# Sensors.net
KiCad netlist of a schematic drawn in Altium Designer
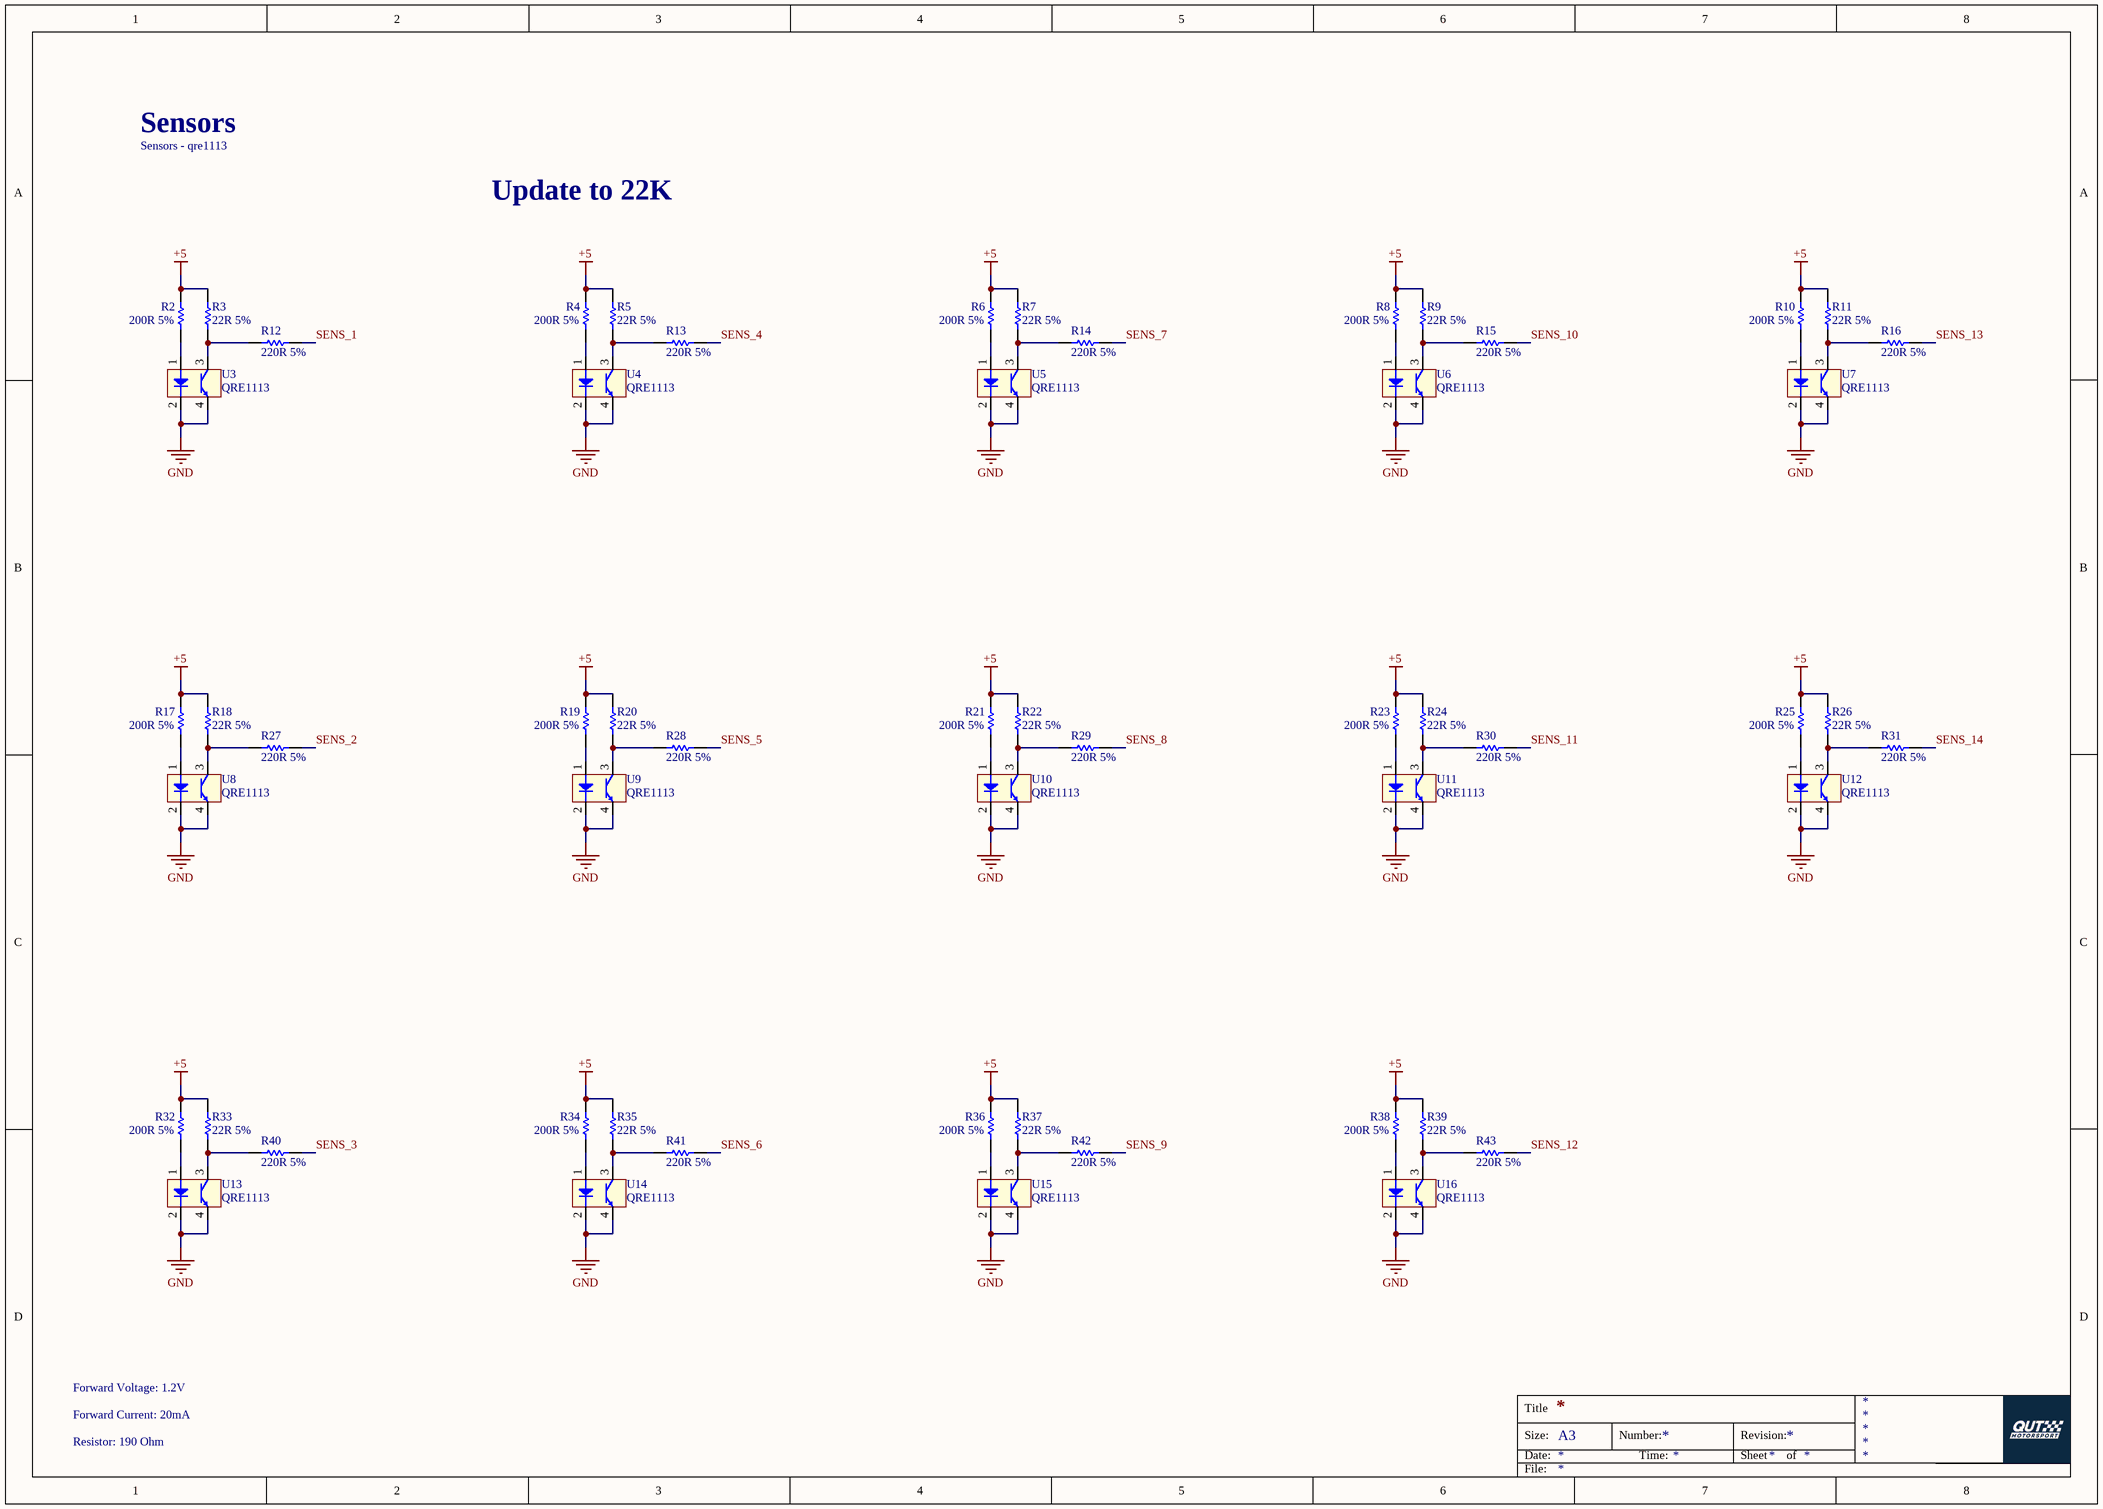
[diagram p0: Sensors.SchDoc]

(export (version "E")
  (design (tool "Eeschema 10.0.6"))
  (components
    (comp (ref "R2")
      (value "200R 5%")
      (footprint "RESC0603(1608)_L")
      (description "200R 0.1W 5% 0603 (1608 Metric)  SMD")
      (fields (field (name "TOLERANCE") "5 %") (field (name "POWER") "0.1 W"))
      (libsource (lib "Altium Content Vault") (part "RES"))
    )
    (comp (ref "R3")
      (value "22R 5%")
      (footprint "RESC0603(1608)_N")
      (description "22R 0.1W 5% 0603 (1608 Metric)  SMD")
      (fields (field (name "POWER") "0.1 W") (field (name "TOLERANCE") "5 %"))
      (libsource (lib "Altium Content Vault") (part "RES"))
    )
    (comp (ref "R4")
      (value "200R 5%")
      (footprint "RESC0603(1608)_L")
      (description "200R 0.1W 5% 0603 (1608 Metric)  SMD")
      (fields (field (name "TOLERANCE") "5 %") (field (name "POWER") "0.1 W"))
      (libsource (lib "Altium Content Vault") (part "RES"))
    )
    (comp (ref "R5")
      (value "22R 5%")
      (footprint "RESC0603(1608)_N")
      (description "22R 0.1W 5% 0603 (1608 Metric)  SMD")
      (fields (field (name "POWER") "0.1 W") (field (name "TOLERANCE") "5 %"))
      (libsource (lib "Altium Content Vault") (part "RES"))
    )
    (comp (ref "R6")
      (value "200R 5%")
      (footprint "RESC0603(1608)_L")
      (description "200R 0.1W 5% 0603 (1608 Metric)  SMD")
      (fields (field (name "TOLERANCE") "5 %") (field (name "POWER") "0.1 W"))
      (libsource (lib "Altium Content Vault") (part "RES"))
    )
    (comp (ref "R7")
      (value "22R 5%")
      (footprint "RESC0603(1608)_N")
      (description "22R 0.1W 5% 0603 (1608 Metric)  SMD")
      (fields (field (name "POWER") "0.1 W") (field (name "TOLERANCE") "5 %"))
      (libsource (lib "Altium Content Vault") (part "RES"))
    )
    (comp (ref "R8")
      (value "200R 5%")
      (footprint "RESC0603(1608)_L")
      (description "200R 0.1W 5% 0603 (1608 Metric)  SMD")
      (fields (field (name "TOLERANCE") "5 %") (field (name "POWER") "0.1 W"))
      (libsource (lib "Altium Content Vault") (part "RES"))
    )
    (comp (ref "R9")
      (value "22R 5%")
      (footprint "RESC0603(1608)_N")
      (description "22R 0.1W 5% 0603 (1608 Metric)  SMD")
      (fields (field (name "POWER") "0.1 W") (field (name "TOLERANCE") "5 %"))
      (libsource (lib "Altium Content Vault") (part "RES"))
    )
    (comp (ref "R10")
      (value "200R 5%")
      (footprint "RESC0603(1608)_L")
      (description "200R 0.1W 5% 0603 (1608 Metric)  SMD")
      (fields (field (name "TOLERANCE") "5 %") (field (name "POWER") "0.1 W"))
      (libsource (lib "Altium Content Vault") (part "RES"))
    )
    (comp (ref "R11")
      (value "22R 5%")
      (footprint "RESC0603(1608)_N")
      (description "22R 0.1W 5% 0603 (1608 Metric)  SMD")
      (fields (field (name "POWER") "0.1 W") (field (name "TOLERANCE") "5 %"))
      (libsource (lib "Altium Content Vault") (part "RES"))
    )
    (comp (ref "R12")
      (value "220R 5%")
      (footprint "RESC0603(1608)_M")
      (description "220R 0.1W 5% 0603 (1608 Metric)  SMD")
      (fields (field (name "POWER") "0.1 W") (field (name "TOLERANCE") "5 %"))
      (libsource (lib "Altium Content Vault") (part "RES"))
    )
    (comp (ref "R13")
      (value "220R 5%")
      (footprint "RESC0603(1608)_M")
      (description "220R 0.1W 5% 0603 (1608 Metric)  SMD")
      (fields (field (name "POWER") "0.1 W") (field (name "TOLERANCE") "5 %"))
      (libsource (lib "Altium Content Vault") (part "RES"))
    )
    (comp (ref "R14")
      (value "220R 5%")
      (footprint "RESC0603(1608)_M")
      (description "220R 0.1W 5% 0603 (1608 Metric)  SMD")
      (fields (field (name "POWER") "0.1 W") (field (name "TOLERANCE") "5 %"))
      (libsource (lib "Altium Content Vault") (part "RES"))
    )
    (comp (ref "R15")
      (value "220R 5%")
      (footprint "RESC0603(1608)_M")
      (description "220R 0.1W 5% 0603 (1608 Metric)  SMD")
      (fields (field (name "POWER") "0.1 W") (field (name "TOLERANCE") "5 %"))
      (libsource (lib "Altium Content Vault") (part "RES"))
    )
    (comp (ref "R16")
      (value "220R 5%")
      (footprint "RESC0603(1608)_M")
      (description "220R 0.1W 5% 0603 (1608 Metric)  SMD")
      (fields (field (name "POWER") "0.1 W") (field (name "TOLERANCE") "5 %"))
      (libsource (lib "Altium Content Vault") (part "RES"))
    )
    (comp (ref "R17")
      (value "200R 5%")
      (footprint "RESC0603(1608)_L")
      (description "200R 0.1W 5% 0603 (1608 Metric)  SMD")
      (fields (field (name "TOLERANCE") "5 %") (field (name "POWER") "0.1 W"))
      (libsource (lib "Altium Content Vault") (part "RES"))
    )
    (comp (ref "R18")
      (value "22R 5%")
      (footprint "RESC0603(1608)_N")
      (description "22R 0.1W 5% 0603 (1608 Metric)  SMD")
      (fields (field (name "POWER") "0.1 W") (field (name "TOLERANCE") "5 %"))
      (libsource (lib "Altium Content Vault") (part "RES"))
    )
    (comp (ref "R19")
      (value "200R 5%")
      (footprint "RESC0603(1608)_L")
      (description "200R 0.1W 5% 0603 (1608 Metric)  SMD")
      (fields (field (name "TOLERANCE") "5 %") (field (name "POWER") "0.1 W"))
      (libsource (lib "Altium Content Vault") (part "RES"))
    )
    (comp (ref "R20")
      (value "22R 5%")
      (footprint "RESC0603(1608)_N")
      (description "22R 0.1W 5% 0603 (1608 Metric)  SMD")
      (fields (field (name "POWER") "0.1 W") (field (name "TOLERANCE") "5 %"))
      (libsource (lib "Altium Content Vault") (part "RES"))
    )
    (comp (ref "R21")
      (value "200R 5%")
      (footprint "RESC0603(1608)_L")
      (description "200R 0.1W 5% 0603 (1608 Metric)  SMD")
      (fields (field (name "TOLERANCE") "5 %") (field (name "POWER") "0.1 W"))
      (libsource (lib "Altium Content Vault") (part "RES"))
    )
    (comp (ref "R22")
      (value "22R 5%")
      (footprint "RESC0603(1608)_N")
      (description "22R 0.1W 5% 0603 (1608 Metric)  SMD")
      (fields (field (name "POWER") "0.1 W") (field (name "TOLERANCE") "5 %"))
      (libsource (lib "Altium Content Vault") (part "RES"))
    )
    (comp (ref "R23")
      (value "200R 5%")
      (footprint "RESC0603(1608)_L")
      (description "200R 0.1W 5% 0603 (1608 Metric)  SMD")
      (fields (field (name "TOLERANCE") "5 %") (field (name "POWER") "0.1 W"))
      (libsource (lib "Altium Content Vault") (part "RES"))
    )
    (comp (ref "R24")
      (value "22R 5%")
      (footprint "RESC0603(1608)_N")
      (description "22R 0.1W 5% 0603 (1608 Metric)  SMD")
      (fields (field (name "POWER") "0.1 W") (field (name "TOLERANCE") "5 %"))
      (libsource (lib "Altium Content Vault") (part "RES"))
    )
    (comp (ref "R25")
      (value "200R 5%")
      (footprint "RESC0603(1608)_L")
      (description "200R 0.1W 5% 0603 (1608 Metric)  SMD")
      (fields (field (name "TOLERANCE") "5 %") (field (name "POWER") "0.1 W"))
      (libsource (lib "Altium Content Vault") (part "RES"))
    )
    (comp (ref "R26")
      (value "22R 5%")
      (footprint "RESC0603(1608)_N")
      (description "22R 0.1W 5% 0603 (1608 Metric)  SMD")
      (fields (field (name "POWER") "0.1 W") (field (name "TOLERANCE") "5 %"))
      (libsource (lib "Altium Content Vault") (part "RES"))
    )
    (comp (ref "R27")
      (value "220R 5%")
      (footprint "RESC0603(1608)_M")
      (description "220R 0.1W 5% 0603 (1608 Metric)  SMD")
      (fields (field (name "POWER") "0.1 W") (field (name "TOLERANCE") "5 %"))
      (libsource (lib "Altium Content Vault") (part "RES"))
    )
    (comp (ref "R28")
      (value "220R 5%")
      (footprint "RESC0603(1608)_M")
      (description "220R 0.1W 5% 0603 (1608 Metric)  SMD")
      (fields (field (name "POWER") "0.1 W") (field (name "TOLERANCE") "5 %"))
      (libsource (lib "Altium Content Vault") (part "RES"))
    )
    (comp (ref "R29")
      (value "220R 5%")
      (footprint "RESC0603(1608)_M")
      (description "220R 0.1W 5% 0603 (1608 Metric)  SMD")
      (fields (field (name "POWER") "0.1 W") (field (name "TOLERANCE") "5 %"))
      (libsource (lib "Altium Content Vault") (part "RES"))
    )
    (comp (ref "R30")
      (value "220R 5%")
      (footprint "RESC0603(1608)_M")
      (description "220R 0.1W 5% 0603 (1608 Metric)  SMD")
      (fields (field (name "POWER") "0.1 W") (field (name "TOLERANCE") "5 %"))
      (libsource (lib "Altium Content Vault") (part "RES"))
    )
    (comp (ref "R31")
      (value "220R 5%")
      (footprint "RESC0603(1608)_M")
      (description "220R 0.1W 5% 0603 (1608 Metric)  SMD")
      (fields (field (name "POWER") "0.1 W") (field (name "TOLERANCE") "5 %"))
      (libsource (lib "Altium Content Vault") (part "RES"))
    )
    (comp (ref "R32")
      (value "200R 5%")
      (footprint "RESC0603(1608)_L")
      (description "200R 0.1W 5% 0603 (1608 Metric)  SMD")
      (fields (field (name "TOLERANCE") "5 %") (field (name "POWER") "0.1 W"))
      (libsource (lib "Altium Content Vault") (part "RES"))
    )
    (comp (ref "R33")
      (value "22R 5%")
      (footprint "RESC0603(1608)_N")
      (description "22R 0.1W 5% 0603 (1608 Metric)  SMD")
      (fields (field (name "POWER") "0.1 W") (field (name "TOLERANCE") "5 %"))
      (libsource (lib "Altium Content Vault") (part "RES"))
    )
    (comp (ref "R34")
      (value "200R 5%")
      (footprint "RESC0603(1608)_L")
      (description "200R 0.1W 5% 0603 (1608 Metric)  SMD")
      (fields (field (name "TOLERANCE") "5 %") (field (name "POWER") "0.1 W"))
      (libsource (lib "Altium Content Vault") (part "RES"))
    )
    (comp (ref "R35")
      (value "22R 5%")
      (footprint "RESC0603(1608)_N")
      (description "22R 0.1W 5% 0603 (1608 Metric)  SMD")
      (fields (field (name "POWER") "0.1 W") (field (name "TOLERANCE") "5 %"))
      (libsource (lib "Altium Content Vault") (part "RES"))
    )
    (comp (ref "R36")
      (value "200R 5%")
      (footprint "RESC0603(1608)_L")
      (description "200R 0.1W 5% 0603 (1608 Metric)  SMD")
      (fields (field (name "TOLERANCE") "5 %") (field (name "POWER") "0.1 W"))
      (libsource (lib "Altium Content Vault") (part "RES"))
    )
    (comp (ref "R37")
      (value "22R 5%")
      (footprint "RESC0603(1608)_N")
      (description "22R 0.1W 5% 0603 (1608 Metric)  SMD")
      (fields (field (name "POWER") "0.1 W") (field (name "TOLERANCE") "5 %"))
      (libsource (lib "Altium Content Vault") (part "RES"))
    )
    (comp (ref "R38")
      (value "200R 5%")
      (footprint "RESC0603(1608)_L")
      (description "200R 0.1W 5% 0603 (1608 Metric)  SMD")
      (fields (field (name "TOLERANCE") "5 %") (field (name "POWER") "0.1 W"))
      (libsource (lib "Altium Content Vault") (part "RES"))
    )
    (comp (ref "R39")
      (value "22R 5%")
      (footprint "RESC0603(1608)_N")
      (description "22R 0.1W 5% 0603 (1608 Metric)  SMD")
      (fields (field (name "POWER") "0.1 W") (field (name "TOLERANCE") "5 %"))
      (libsource (lib "Altium Content Vault") (part "RES"))
    )
    (comp (ref "R40")
      (value "220R 5%")
      (footprint "RESC0603(1608)_M")
      (description "220R 0.1W 5% 0603 (1608 Metric)  SMD")
      (fields (field (name "POWER") "0.1 W") (field (name "TOLERANCE") "5 %"))
      (libsource (lib "Altium Content Vault") (part "RES"))
    )
    (comp (ref "R41")
      (value "220R 5%")
      (footprint "RESC0603(1608)_M")
      (description "220R 0.1W 5% 0603 (1608 Metric)  SMD")
      (fields (field (name "POWER") "0.1 W") (field (name "TOLERANCE") "5 %"))
      (libsource (lib "Altium Content Vault") (part "RES"))
    )
    (comp (ref "R42")
      (value "220R 5%")
      (footprint "RESC0603(1608)_M")
      (description "220R 0.1W 5% 0603 (1608 Metric)  SMD")
      (fields (field (name "POWER") "0.1 W") (field (name "TOLERANCE") "5 %"))
      (libsource (lib "Altium Content Vault") (part "RES"))
    )
    (comp (ref "R43")
      (value "220R 5%")
      (footprint "RESC0603(1608)_M")
      (description "220R 0.1W 5% 0603 (1608 Metric)  SMD")
      (fields (field (name "POWER") "0.1 W") (field (name "TOLERANCE") "5 %"))
      (libsource (lib "Altium Content Vault") (part "RES"))
    )
    (comp (ref "U3") (value "QRE1113") (footprint "QRE1113GR") (libsource (lib "EGB220") (part "QRE1113")))
    (comp (ref "U4") (value "QRE1113") (footprint "QRE1113GR") (libsource (lib "EGB220") (part "QRE1113")))
    (comp (ref "U5") (value "QRE1113") (footprint "QRE1113GR") (libsource (lib "EGB220") (part "QRE1113")))
    (comp (ref "U6") (value "QRE1113") (footprint "QRE1113GR") (libsource (lib "EGB220") (part "QRE1113")))
    (comp (ref "U7") (value "QRE1113") (footprint "QRE1113GR") (libsource (lib "EGB220") (part "QRE1113")))
    (comp (ref "U8") (value "QRE1113") (footprint "QRE1113GR") (libsource (lib "EGB220") (part "QRE1113")))
    (comp (ref "U9") (value "QRE1113") (footprint "QRE1113GR") (libsource (lib "EGB220") (part "QRE1113")))
    (comp (ref "U10") (value "QRE1113") (footprint "QRE1113GR") (libsource (lib "EGB220") (part "QRE1113")))
    (comp (ref "U11") (value "QRE1113") (footprint "QRE1113GR") (libsource (lib "EGB220") (part "QRE1113")))
    (comp (ref "U12") (value "QRE1113") (footprint "QRE1113GR") (libsource (lib "EGB220") (part "QRE1113")))
    (comp (ref "U13") (value "QRE1113") (footprint "QRE1113GR") (libsource (lib "EGB220") (part "QRE1113")))
    (comp (ref "U14") (value "QRE1113") (footprint "QRE1113GR") (libsource (lib "EGB220") (part "QRE1113")))
    (comp (ref "U15") (value "QRE1113") (footprint "QRE1113GR") (libsource (lib "EGB220") (part "QRE1113")))
    (comp (ref "U16") (value "QRE1113") (footprint "QRE1113GR") (libsource (lib "EGB220") (part "QRE1113")))
  )
  (nets
    (net (code "1") (name "+5") (class "Default")
      (node (ref "R10") (pin "2") (pinfunction "2_2") (pintype "passive"))
      (node (ref "R11") (pin "2") (pinfunction "2_2") (pintype "passive"))
      (node (ref "R17") (pin "2") (pinfunction "2_2") (pintype "passive"))
      (node (ref "R18") (pin "2") (pinfunction "2_2") (pintype "passive"))
      (node (ref "R19") (pin "2") (pinfunction "2_2") (pintype "passive"))
      (node (ref "R2") (pin "2") (pinfunction "2_2") (pintype "passive"))
      (node (ref "R20") (pin "2") (pinfunction "2_2") (pintype "passive"))
      (node (ref "R21") (pin "2") (pinfunction "2_2") (pintype "passive"))
      (node (ref "R22") (pin "2") (pinfunction "2_2") (pintype "passive"))
      (node (ref "R23") (pin "2") (pinfunction "2_2") (pintype "passive"))
      (node (ref "R24") (pin "2") (pinfunction "2_2") (pintype "passive"))
      (node (ref "R25") (pin "2") (pinfunction "2_2") (pintype "passive"))
      (node (ref "R26") (pin "2") (pinfunction "2_2") (pintype "passive"))
      (node (ref "R3") (pin "2") (pinfunction "2_2") (pintype "passive"))
      (node (ref "R32") (pin "2") (pinfunction "2_2") (pintype "passive"))
      (node (ref "R33") (pin "2") (pinfunction "2_2") (pintype "passive"))
      (node (ref "R34") (pin "2") (pinfunction "2_2") (pintype "passive"))
      (node (ref "R35") (pin "2") (pinfunction "2_2") (pintype "passive"))
      (node (ref "R36") (pin "2") (pinfunction "2_2") (pintype "passive"))
      (node (ref "R37") (pin "2") (pinfunction "2_2") (pintype "passive"))
      (node (ref "R38") (pin "2") (pinfunction "2_2") (pintype "passive"))
      (node (ref "R39") (pin "2") (pinfunction "2_2") (pintype "passive"))
      (node (ref "R4") (pin "2") (pinfunction "2_2") (pintype "passive"))
      (node (ref "R5") (pin "2") (pinfunction "2_2") (pintype "passive"))
      (node (ref "R6") (pin "2") (pinfunction "2_2") (pintype "passive"))
      (node (ref "R7") (pin "2") (pinfunction "2_2") (pintype "passive"))
      (node (ref "R8") (pin "2") (pinfunction "2_2") (pintype "passive"))
      (node (ref "R9") (pin "2") (pinfunction "2_2") (pintype "passive"))
    )
    (net (code "2") (name "/SENS_1") (class "Default")
      (node (ref "R12") (pin "2") (pinfunction "2_2") (pintype "passive"))
    )
    (net (code "3") (name "/SENS_2") (class "Default")
      (node (ref "R27") (pin "2") (pinfunction "2_2") (pintype "passive"))
    )
    (net (code "4") (name "/SENS_3") (class "Default")
      (node (ref "R40") (pin "2") (pinfunction "2_2") (pintype "passive"))
    )
    (net (code "5") (name "/SENS_4") (class "Default")
      (node (ref "R13") (pin "2") (pinfunction "2_2") (pintype "passive"))
    )
    (net (code "6") (name "/SENS_5") (class "Default")
      (node (ref "R28") (pin "2") (pinfunction "2_2") (pintype "passive"))
    )
    (net (code "7") (name "/SENS_6") (class "Default")
      (node (ref "R41") (pin "2") (pinfunction "2_2") (pintype "passive"))
    )
    (net (code "8") (name "/SENS_7") (class "Default")
      (node (ref "R14") (pin "2") (pinfunction "2_2") (pintype "passive"))
    )
    (net (code "9") (name "/SENS_8") (class "Default")
      (node (ref "R29") (pin "2") (pinfunction "2_2") (pintype "passive"))
    )
    (net (code "10") (name "/SENS_9") (class "Default")
      (node (ref "R42") (pin "2") (pinfunction "2_2") (pintype "passive"))
    )
    (net (code "11") (name "/SENS_10") (class "Default")
      (node (ref "R15") (pin "2") (pinfunction "2_2") (pintype "passive"))
    )
    (net (code "12") (name "/SENS_11") (class "Default")
      (node (ref "R30") (pin "2") (pinfunction "2_2") (pintype "passive"))
    )
    (net (code "13") (name "/SENS_12") (class "Default")
      (node (ref "R43") (pin "2") (pinfunction "2_2") (pintype "passive"))
    )
    (net (code "14") (name "/SENS_13") (class "Default")
      (node (ref "R16") (pin "2") (pinfunction "2_2") (pintype "passive"))
    )
    (net (code "15") (name "/SENS_14") (class "Default")
      (node (ref "R31") (pin "2") (pinfunction "2_2") (pintype "passive"))
    )
    (net (code "16") (name "GND") (class "Default")
      (node (ref "U10") (pin "2") (pinfunction "2_2") (pintype "passive"))
      (node (ref "U10") (pin "4") (pinfunction "4_4") (pintype "passive"))
      (node (ref "U11") (pin "2") (pinfunction "2_2") (pintype "passive"))
      (node (ref "U11") (pin "4") (pinfunction "4_4") (pintype "passive"))
      (node (ref "U12") (pin "2") (pinfunction "2_2") (pintype "passive"))
      (node (ref "U12") (pin "4") (pinfunction "4_4") (pintype "passive"))
      (node (ref "U13") (pin "2") (pinfunction "2_2") (pintype "passive"))
      (node (ref "U13") (pin "4") (pinfunction "4_4") (pintype "passive"))
      (node (ref "U14") (pin "2") (pinfunction "2_2") (pintype "passive"))
      (node (ref "U14") (pin "4") (pinfunction "4_4") (pintype "passive"))
      (node (ref "U15") (pin "2") (pinfunction "2_2") (pintype "passive"))
      (node (ref "U15") (pin "4") (pinfunction "4_4") (pintype "passive"))
      (node (ref "U16") (pin "2") (pinfunction "2_2") (pintype "passive"))
      (node (ref "U16") (pin "4") (pinfunction "4_4") (pintype "passive"))
      (node (ref "U3") (pin "2") (pinfunction "2_2") (pintype "passive"))
      (node (ref "U3") (pin "4") (pinfunction "4_4") (pintype "passive"))
      (node (ref "U4") (pin "2") (pinfunction "2_2") (pintype "passive"))
      (node (ref "U4") (pin "4") (pinfunction "4_4") (pintype "passive"))
      (node (ref "U5") (pin "2") (pinfunction "2_2") (pintype "passive"))
      (node (ref "U5") (pin "4") (pinfunction "4_4") (pintype "passive"))
      (node (ref "U6") (pin "2") (pinfunction "2_2") (pintype "passive"))
      (node (ref "U6") (pin "4") (pinfunction "4_4") (pintype "passive"))
      (node (ref "U7") (pin "2") (pinfunction "2_2") (pintype "passive"))
      (node (ref "U7") (pin "4") (pinfunction "4_4") (pintype "passive"))
      (node (ref "U8") (pin "2") (pinfunction "2_2") (pintype "passive"))
      (node (ref "U8") (pin "4") (pinfunction "4_4") (pintype "passive"))
      (node (ref "U9") (pin "2") (pinfunction "2_2") (pintype "passive"))
      (node (ref "U9") (pin "4") (pinfunction "4_4") (pintype "passive"))
    )
    (net (code "17") (name "Net-(R11-Pad1)") (class "Default")
      (node (ref "R11") (pin "1") (pinfunction "1_1") (pintype "passive"))
      (node (ref "R16") (pin "1") (pinfunction "1_1") (pintype "passive"))
      (node (ref "U7") (pin "3") (pinfunction "3_3") (pintype "passive"))
    )
    (net (code "18") (name "Net-(R12-Pad1)") (class "Default")
      (node (ref "R12") (pin "1") (pinfunction "1_1") (pintype "passive"))
      (node (ref "R3") (pin "1") (pinfunction "1_1") (pintype "passive"))
      (node (ref "U3") (pin "3") (pinfunction "3_3") (pintype "passive"))
    )
    (net (code "19") (name "Net-(R13-Pad1)") (class "Default")
      (node (ref "R13") (pin "1") (pinfunction "1_1") (pintype "passive"))
      (node (ref "R5") (pin "1") (pinfunction "1_1") (pintype "passive"))
      (node (ref "U4") (pin "3") (pinfunction "3_3") (pintype "passive"))
    )
    (net (code "20") (name "Net-(R14-Pad1)") (class "Default")
      (node (ref "R14") (pin "1") (pinfunction "1_1") (pintype "passive"))
      (node (ref "R7") (pin "1") (pinfunction "1_1") (pintype "passive"))
      (node (ref "U5") (pin "3") (pinfunction "3_3") (pintype "passive"))
    )
    (net (code "21") (name "Net-(R15-Pad1)") (class "Default")
      (node (ref "R15") (pin "1") (pinfunction "1_1") (pintype "passive"))
      (node (ref "R9") (pin "1") (pinfunction "1_1") (pintype "passive"))
      (node (ref "U6") (pin "3") (pinfunction "3_3") (pintype "passive"))
    )
    (net (code "22") (name "Net-(R18-Pad1)") (class "Default")
      (node (ref "R18") (pin "1") (pinfunction "1_1") (pintype "passive"))
      (node (ref "R27") (pin "1") (pinfunction "1_1") (pintype "passive"))
      (node (ref "U8") (pin "3") (pinfunction "3_3") (pintype "passive"))
    )
    (net (code "23") (name "Net-(R20-Pad1)") (class "Default")
      (node (ref "R20") (pin "1") (pinfunction "1_1") (pintype "passive"))
      (node (ref "R28") (pin "1") (pinfunction "1_1") (pintype "passive"))
      (node (ref "U9") (pin "3") (pinfunction "3_3") (pintype "passive"))
    )
    (net (code "24") (name "Net-(R22-Pad1)") (class "Default")
      (node (ref "R22") (pin "1") (pinfunction "1_1") (pintype "passive"))
      (node (ref "R29") (pin "1") (pinfunction "1_1") (pintype "passive"))
      (node (ref "U10") (pin "3") (pinfunction "3_3") (pintype "passive"))
    )
    (net (code "25") (name "Net-(R24-Pad1)") (class "Default")
      (node (ref "R24") (pin "1") (pinfunction "1_1") (pintype "passive"))
      (node (ref "R30") (pin "1") (pinfunction "1_1") (pintype "passive"))
      (node (ref "U11") (pin "3") (pinfunction "3_3") (pintype "passive"))
    )
    (net (code "26") (name "Net-(R26-Pad1)") (class "Default")
      (node (ref "R26") (pin "1") (pinfunction "1_1") (pintype "passive"))
      (node (ref "R31") (pin "1") (pinfunction "1_1") (pintype "passive"))
      (node (ref "U12") (pin "3") (pinfunction "3_3") (pintype "passive"))
    )
    (net (code "27") (name "Net-(R33-Pad1)") (class "Default")
      (node (ref "R33") (pin "1") (pinfunction "1_1") (pintype "passive"))
      (node (ref "R40") (pin "1") (pinfunction "1_1") (pintype "passive"))
      (node (ref "U13") (pin "3") (pinfunction "3_3") (pintype "passive"))
    )
    (net (code "28") (name "Net-(R35-Pad1)") (class "Default")
      (node (ref "R35") (pin "1") (pinfunction "1_1") (pintype "passive"))
      (node (ref "R41") (pin "1") (pinfunction "1_1") (pintype "passive"))
      (node (ref "U14") (pin "3") (pinfunction "3_3") (pintype "passive"))
    )
    (net (code "29") (name "Net-(R37-Pad1)") (class "Default")
      (node (ref "R37") (pin "1") (pinfunction "1_1") (pintype "passive"))
      (node (ref "R42") (pin "1") (pinfunction "1_1") (pintype "passive"))
      (node (ref "U15") (pin "3") (pinfunction "3_3") (pintype "passive"))
    )
    (net (code "30") (name "Net-(R39-Pad1)") (class "Default")
      (node (ref "R39") (pin "1") (pinfunction "1_1") (pintype "passive"))
      (node (ref "R43") (pin "1") (pinfunction "1_1") (pintype "passive"))
      (node (ref "U16") (pin "3") (pinfunction "3_3") (pintype "passive"))
    )
    (net (code "31") (name "Net-(U3-0)") (class "Default")
      (node (ref "R2") (pin "1") (pinfunction "1_1") (pintype "passive"))
      (node (ref "U3") (pin "1") (pinfunction "0_1") (pintype "passive"))
    )
    (net (code "32") (name "Net-(U4-0)") (class "Default")
      (node (ref "R4") (pin "1") (pinfunction "1_1") (pintype "passive"))
      (node (ref "U4") (pin "1") (pinfunction "0_1") (pintype "passive"))
    )
    (net (code "33") (name "Net-(U5-0)") (class "Default")
      (node (ref "R6") (pin "1") (pinfunction "1_1") (pintype "passive"))
      (node (ref "U5") (pin "1") (pinfunction "0_1") (pintype "passive"))
    )
    (net (code "34") (name "Net-(U6-0)") (class "Default")
      (node (ref "R8") (pin "1") (pinfunction "1_1") (pintype "passive"))
      (node (ref "U6") (pin "1") (pinfunction "0_1") (pintype "passive"))
    )
    (net (code "35") (name "Net-(U7-0)") (class "Default")
      (node (ref "R10") (pin "1") (pinfunction "1_1") (pintype "passive"))
      (node (ref "U7") (pin "1") (pinfunction "0_1") (pintype "passive"))
    )
    (net (code "36") (name "Net-(U8-0)") (class "Default")
      (node (ref "R17") (pin "1") (pinfunction "1_1") (pintype "passive"))
      (node (ref "U8") (pin "1") (pinfunction "0_1") (pintype "passive"))
    )
    (net (code "37") (name "Net-(U9-0)") (class "Default")
      (node (ref "R19") (pin "1") (pinfunction "1_1") (pintype "passive"))
      (node (ref "U9") (pin "1") (pinfunction "0_1") (pintype "passive"))
    )
    (net (code "38") (name "Net-(U10-0)") (class "Default")
      (node (ref "R21") (pin "1") (pinfunction "1_1") (pintype "passive"))
      (node (ref "U10") (pin "1") (pinfunction "0_1") (pintype "passive"))
    )
    (net (code "39") (name "Net-(U11-0)") (class "Default")
      (node (ref "R23") (pin "1") (pinfunction "1_1") (pintype "passive"))
      (node (ref "U11") (pin "1") (pinfunction "0_1") (pintype "passive"))
    )
    (net (code "40") (name "Net-(U12-0)") (class "Default")
      (node (ref "R25") (pin "1") (pinfunction "1_1") (pintype "passive"))
      (node (ref "U12") (pin "1") (pinfunction "0_1") (pintype "passive"))
    )
    (net (code "41") (name "Net-(U13-0)") (class "Default")
      (node (ref "R32") (pin "1") (pinfunction "1_1") (pintype "passive"))
      (node (ref "U13") (pin "1") (pinfunction "0_1") (pintype "passive"))
    )
    (net (code "42") (name "Net-(U14-0)") (class "Default")
      (node (ref "R34") (pin "1") (pinfunction "1_1") (pintype "passive"))
      (node (ref "U14") (pin "1") (pinfunction "0_1") (pintype "passive"))
    )
    (net (code "43") (name "Net-(U15-0)") (class "Default")
      (node (ref "R36") (pin "1") (pinfunction "1_1") (pintype "passive"))
      (node (ref "U15") (pin "1") (pinfunction "0_1") (pintype "passive"))
    )
    (net (code "44") (name "Net-(U16-0)") (class "Default")
      (node (ref "R38") (pin "1") (pinfunction "1_1") (pintype "passive"))
      (node (ref "U16") (pin "1") (pinfunction "0_1") (pintype "passive"))
    )
  )
)
